# SafeCharge.net
KiCad netlist of a schematic drawn in Altium Designer
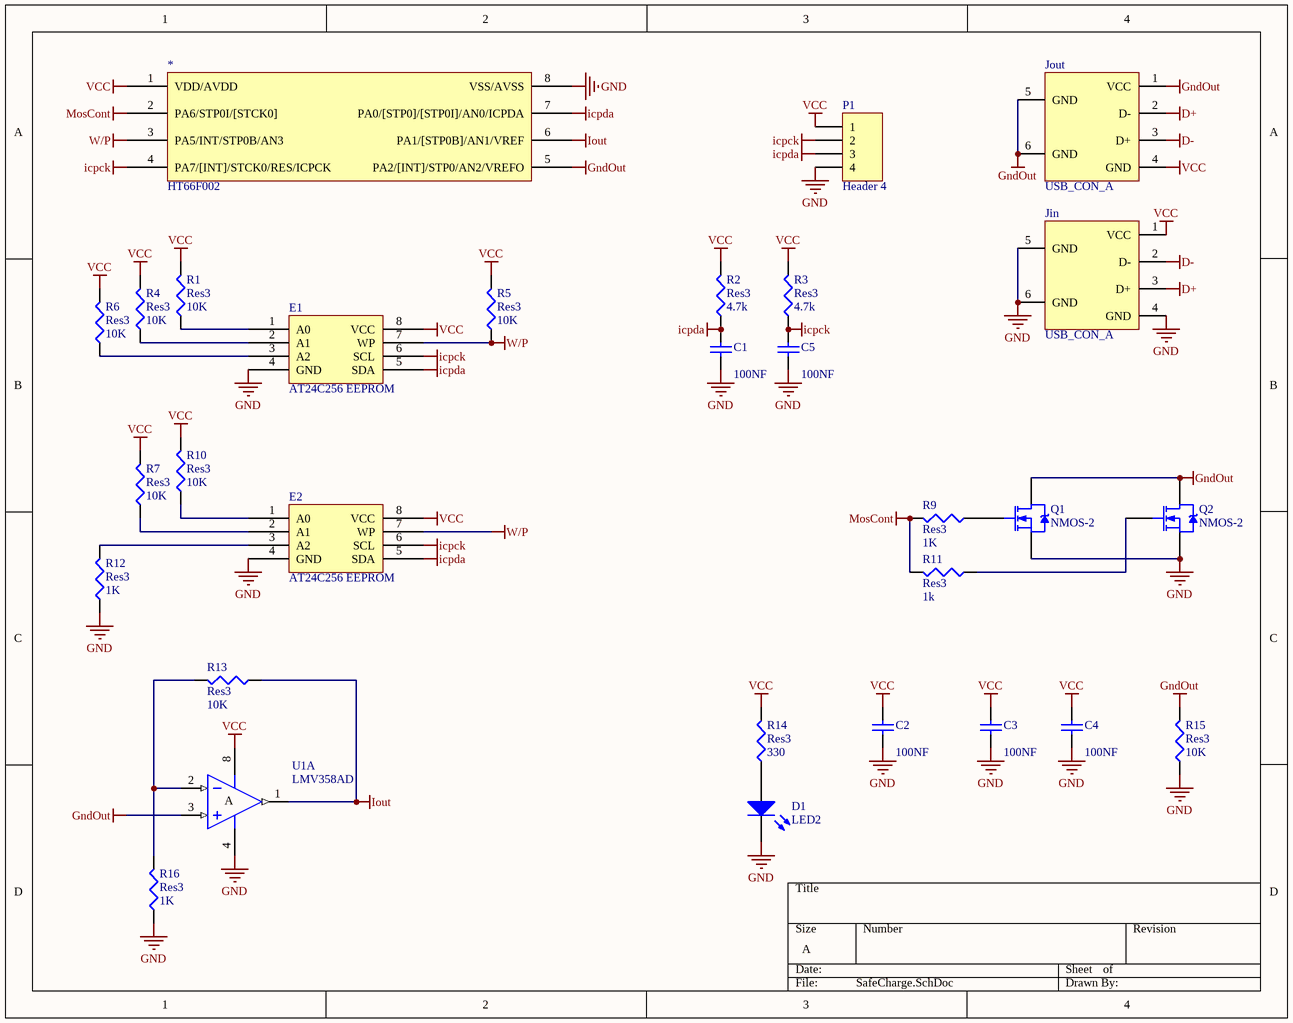
[diagram p0: SafeCharge.SchDoc]

(export (version "E")
  (design (tool "Eeschema 10.0.6"))
  (components
    (comp (ref "*") (value "HT66F002") (footprint "SO8") (libsource (lib "myLib") (part "HT66F002")))
    (comp (ref "C1")
      (value "100NF")
      (footprint "6-0805_N")
      (description "Capacitor (Semiconductor SIM Model)")
      (fields (field (name "Comment") "Cap Semi") (field (name "PUBLISHER") "Altium Limited"))
      (libsource (lib "Miscellaneous Devices") (part "Cap Semi"))
    )
    (comp (ref "C2")
      (value "100NF")
      (footprint "6-0805_N")
      (description "Capacitor (Semiconductor SIM Model)")
      (fields (field (name "Comment") "Cap Semi") (field (name "PUBLISHER") "Altium Limited"))
      (libsource (lib "Miscellaneous Devices") (part "Cap Semi"))
    )
    (comp (ref "C3")
      (value "100NF")
      (footprint "6-0805_N")
      (description "Capacitor (Semiconductor SIM Model)")
      (fields (field (name "Comment") "Cap Semi") (field (name "PUBLISHER") "Altium Limited"))
      (libsource (lib "Miscellaneous Devices") (part "Cap Semi"))
    )
    (comp (ref "C4")
      (value "100NF")
      (footprint "6-0805_N")
      (description "Capacitor (Semiconductor SIM Model)")
      (fields (field (name "Comment") "Cap Semi") (field (name "PUBLISHER") "Altium Limited"))
      (libsource (lib "Miscellaneous Devices") (part "Cap Semi"))
    )
    (comp (ref "C5")
      (value "100NF")
      (footprint "6-0805_N")
      (description "Capacitor (Semiconductor SIM Model)")
      (fields (field (name "Comment") "Cap Semi") (field (name "PUBLISHER") "Altium Limited"))
      (libsource (lib "Miscellaneous Devices") (part "Cap Semi"))
    )
    (comp (ref "D1")
      (value "LED2")
      (footprint "C1206")
      (description "Typical RED, GREEN, YELLOW, AMBER GaAs LED")
      (fields (field (name "PUBLISHER") "Altium Limited"))
      (libsource (lib "Miscellaneous Devices") (part "LED2"))
    )
    (comp (ref "E1")
      (value "AT24C256 EEPROM")
      (footprint "SOIC8_L")
      (libsource (lib "24C256 SHC") (part "AT24C256 EEPROM"))
    )
    (comp (ref "E2")
      (value "AT24C256 EEPROM")
      (footprint "SOIC8_L")
      (libsource (lib "24C256 SHC") (part "AT24C256 EEPROM"))
    )
    (comp (ref "Jin")
      (value "USB_CON_A")
      (footprint "USB_CON_A")
      (libsource (lib "SchLib299") (part "USB_CON_A"))
    )
    (comp (ref "Jout")
      (value "USB_CON_A")
      (footprint "USB_CON_A")
      (libsource (lib "SchLib299") (part "USB_CON_A"))
    )
    (comp (ref "P1")
      (value "Header 4")
      (footprint "HDR1X4")
      (description "Header, 4-Pin")
      (fields (field (name "PUBLISHER") "Altium Limited"))
      (libsource (lib "Miscellaneous Connectors") (part "Header 4"))
    )
    (comp (ref "Q1")
      (value "NMOS-2")
      (footprint "SOT-23_N")
      (description "N-Channel Power MOSFET")
      (fields (field (name "PUBLISHER") "Altium Limited"))
      (libsource (lib "Miscellaneous Devices") (part "NMOS-2"))
    )
    (comp (ref "Q2")
      (value "NMOS-2")
      (footprint "SOT-23_N")
      (description "N-Channel Power MOSFET")
      (fields (field (name "PUBLISHER") "Altium Limited"))
      (libsource (lib "Miscellaneous Devices") (part "NMOS-2"))
    )
    (comp (ref "R1")
      (value "Res3")
      (footprint "6-0805_N")
      (description "Resistor")
      (fields (field (name "ALTIUM_VALUE") "10K") (field (name "PUBLISHER") "Altium Limited"))
      (libsource (lib "Miscellaneous Devices") (part "Res3"))
    )
    (comp (ref "R2")
      (value "Res3")
      (footprint "6-0805_N")
      (description "Resistor")
      (fields (field (name "ALTIUM_VALUE") "4.7k") (field (name "PUBLISHER") "Altium Limited"))
      (libsource (lib "Miscellaneous Devices") (part "Res3"))
    )
    (comp (ref "R3")
      (value "Res3")
      (footprint "6-0805_N")
      (description "Resistor")
      (fields (field (name "ALTIUM_VALUE") "4.7k") (field (name "PUBLISHER") "Altium Limited"))
      (libsource (lib "Miscellaneous Devices") (part "Res3"))
    )
    (comp (ref "R4")
      (value "Res3")
      (footprint "6-0805_N")
      (description "Resistor")
      (fields (field (name "ALTIUM_VALUE") "10K") (field (name "PUBLISHER") "Altium Limited"))
      (libsource (lib "Miscellaneous Devices") (part "Res3"))
    )
    (comp (ref "R5")
      (value "Res3")
      (footprint "6-0805_N")
      (description "Resistor")
      (fields (field (name "ALTIUM_VALUE") "10K") (field (name "PUBLISHER") "Altium Limited"))
      (libsource (lib "Miscellaneous Devices") (part "Res3"))
    )
    (comp (ref "R6")
      (value "Res3")
      (footprint "6-0805_N")
      (description "Resistor")
      (fields (field (name "ALTIUM_VALUE") "10K") (field (name "PUBLISHER") "Altium Limited"))
      (libsource (lib "Miscellaneous Devices") (part "Res3"))
    )
    (comp (ref "R7")
      (value "Res3")
      (footprint "6-0805_N")
      (description "Resistor")
      (fields (field (name "ALTIUM_VALUE") "10K") (field (name "PUBLISHER") "Altium Limited"))
      (libsource (lib "Miscellaneous Devices") (part "Res3"))
    )
    (comp (ref "R9")
      (value "Res3")
      (footprint "6-0805_N")
      (description "Resistor")
      (fields (field (name "ALTIUM_VALUE") "1K") (field (name "PUBLISHER") "Altium Limited"))
      (libsource (lib "Miscellaneous Devices") (part "Res3"))
    )
    (comp (ref "R10")
      (value "Res3")
      (footprint "6-0805_N")
      (description "Resistor")
      (fields (field (name "ALTIUM_VALUE") "10K") (field (name "PUBLISHER") "Altium Limited"))
      (libsource (lib "Miscellaneous Devices") (part "Res3"))
    )
    (comp (ref "R11")
      (value "Res3")
      (footprint "6-0805_N")
      (description "Resistor")
      (fields (field (name "ALTIUM_VALUE") "1k") (field (name "PUBLISHER") "Altium Limited"))
      (libsource (lib "Miscellaneous Devices") (part "Res3"))
    )
    (comp (ref "R12")
      (value "Res3")
      (footprint "6-0805_N")
      (description "Resistor")
      (fields (field (name "ALTIUM_VALUE") "1K") (field (name "PUBLISHER") "Altium Limited"))
      (libsource (lib "Miscellaneous Devices") (part "Res3"))
    )
    (comp (ref "R13")
      (value "Res3")
      (footprint "6-0805_N")
      (description "Resistor")
      (fields (field (name "ALTIUM_VALUE") "10K") (field (name "PUBLISHER") "Altium Limited"))
      (libsource (lib "Miscellaneous Devices") (part "Res3"))
    )
    (comp (ref "R14")
      (value "Res3")
      (footprint "6-0805_N")
      (description "Resistor")
      (fields (field (name "ALTIUM_VALUE") "330") (field (name "PUBLISHER") "Altium Limited"))
      (libsource (lib "Miscellaneous Devices") (part "Res3"))
    )
    (comp (ref "R15")
      (value "Res3")
      (footprint "6-0805_N")
      (description "Resistor")
      (fields (field (name "ALTIUM_VALUE") "10K") (field (name "PUBLISHER") "Altium Limited"))
      (libsource (lib "Miscellaneous Devices") (part "Res3"))
    )
    (comp (ref "R16")
      (value "Res3")
      (footprint "6-0805_N")
      (description "Resistor")
      (fields (field (name "ALTIUM_VALUE") "1K") (field (name "PUBLISHER") "Altium Limited"))
      (libsource (lib "Miscellaneous Devices") (part "Res3"))
    )
    (comp (ref "U1")
      (value "LMV358AD")
      (footprint "SO8_N")
      (description "Low-Power Dual Operational Amplifier")
      (fields (field (name "PUBLISHER") "Altium Limited"))
      (libsource (lib "ST Operational Amplifier") (part "LM358AD"))
    )
  )
  (nets
    (net (code "1") (name "D+") (class "Default")
      (node (ref "Jin") (pin "3") (pinfunction "D+_3") (pintype "passive"))
      (node (ref "Jout") (pin "2") (pinfunction "D-_2") (pintype "passive"))
    )
    (net (code "2") (name "D-") (class "Default")
      (node (ref "Jin") (pin "2") (pinfunction "D-_2") (pintype "passive"))
      (node (ref "Jout") (pin "3") (pinfunction "D+_3") (pintype "passive"))
    )
    (net (code "3") (name "GND") (class "Default")
      (node (ref "*") (pin "8") (pinfunction "VSS/AVSS_8") (pintype "passive"))
      (node (ref "C1") (pin "1") (pinfunction "1_1") (pintype "passive"))
      (node (ref "C2") (pin "1") (pinfunction "1_1") (pintype "passive"))
      (node (ref "C3") (pin "1") (pinfunction "1_1") (pintype "passive"))
      (node (ref "C4") (pin "1") (pinfunction "1_1") (pintype "passive"))
      (node (ref "C5") (pin "1") (pinfunction "1_1") (pintype "passive"))
      (node (ref "D1") (pin "2") (pinfunction "K_2") (pintype "passive"))
      (node (ref "E1") (pin "4") (pinfunction "GND_4") (pintype "passive"))
      (node (ref "E2") (pin "4") (pinfunction "GND_4") (pintype "passive"))
      (node (ref "Jin") (pin "4") (pinfunction "GND_4") (pintype "passive"))
      (node (ref "Jin") (pin "5") (pinfunction "GND_5") (pintype "passive"))
      (node (ref "Jin") (pin "6") (pinfunction "GND_6") (pintype "passive"))
      (node (ref "P1") (pin "4") (pinfunction "4_4") (pintype "passive"))
      (node (ref "Q1") (pin "3") (pinfunction "S_3") (pintype "passive"))
      (node (ref "Q2") (pin "3") (pinfunction "S_3") (pintype "passive"))
      (node (ref "R12") (pin "1") (pinfunction "1_1") (pintype "passive"))
      (node (ref "R15") (pin "1") (pinfunction "1_1") (pintype "passive"))
      (node (ref "R16") (pin "1") (pinfunction "1_1") (pintype "passive"))
      (node (ref "U1") (pin "4") (pinfunction "V-_4") (pintype "power_in"))
    )
    (net (code "4") (name "GndOut") (class "Default")
      (node (ref "*") (pin "5") (pinfunction "PA2/[INT]/STP0/AN2/VREFO_5") (pintype "passive"))
      (node (ref "Jout") (pin "1") (pinfunction "VCC_1") (pintype "passive"))
      (node (ref "Jout") (pin "5") (pinfunction "GND_5") (pintype "passive"))
      (node (ref "Jout") (pin "6") (pinfunction "GND_6") (pintype "passive"))
      (node (ref "Q1") (pin "2") (pinfunction "D_2") (pintype "passive"))
      (node (ref "Q2") (pin "2") (pinfunction "D_2") (pintype "passive"))
      (node (ref "R15") (pin "2") (pinfunction "2_2") (pintype "passive"))
      (node (ref "U1") (pin "3") (pinfunction "IN+_3") (pintype "input"))
    )
    (net (code "5") (name "Iout") (class "Default")
      (node (ref "*") (pin "6") (pinfunction "PA1/[STP0B]/AN1/VREF_6") (pintype "passive"))
      (node (ref "R13") (pin "1") (pinfunction "1_1") (pintype "passive"))
      (node (ref "U1") (pin "1") (pinfunction "OUT_1") (pintype "output"))
    )
    (net (code "6") (name "MosCont") (class "Default")
      (node (ref "*") (pin "2") (pinfunction "PA6/STP0I/[STCK0]_2") (pintype "passive"))
      (node (ref "R11") (pin "2") (pinfunction "2_2") (pintype "passive"))
      (node (ref "R9") (pin "2") (pinfunction "2_2") (pintype "passive"))
    )
    (net (code "7") (name "Net-(D1-A)") (class "Default")
      (node (ref "D1") (pin "1") (pinfunction "A_1") (pintype "passive"))
      (node (ref "R14") (pin "1") (pinfunction "1_1") (pintype "passive"))
    )
    (net (code "8") (name "Net-(E1-A0)") (class "Default")
      (node (ref "E1") (pin "1") (pinfunction "A0_1") (pintype "passive"))
      (node (ref "R1") (pin "1") (pinfunction "1_1") (pintype "passive"))
    )
    (net (code "9") (name "Net-(E1-A1)") (class "Default")
      (node (ref "E1") (pin "2") (pinfunction "A1_2") (pintype "passive"))
      (node (ref "R4") (pin "1") (pinfunction "1_1") (pintype "passive"))
    )
    (net (code "10") (name "Net-(E1-A2)") (class "Default")
      (node (ref "E1") (pin "3") (pinfunction "A2_3") (pintype "passive"))
      (node (ref "R6") (pin "1") (pinfunction "1_1") (pintype "passive"))
    )
    (net (code "11") (name "Net-(E2-A0)") (class "Default")
      (node (ref "E2") (pin "1") (pinfunction "A0_1") (pintype "passive"))
      (node (ref "R10") (pin "1") (pinfunction "1_1") (pintype "passive"))
    )
    (net (code "12") (name "Net-(E2-A1)") (class "Default")
      (node (ref "E2") (pin "2") (pinfunction "A1_2") (pintype "passive"))
      (node (ref "R7") (pin "1") (pinfunction "1_1") (pintype "passive"))
    )
    (net (code "13") (name "Net-(E2-A2)") (class "Default")
      (node (ref "E2") (pin "3") (pinfunction "A2_3") (pintype "passive"))
      (node (ref "R12") (pin "2") (pinfunction "2_2") (pintype "passive"))
    )
    (net (code "14") (name "Net-(Q1-G)") (class "Default")
      (node (ref "Q1") (pin "1") (pinfunction "G_1") (pintype "passive"))
      (node (ref "R9") (pin "1") (pinfunction "1_1") (pintype "passive"))
    )
    (net (code "15") (name "Net-(Q2-G)") (class "Default")
      (node (ref "Q2") (pin "1") (pinfunction "G_1") (pintype "passive"))
      (node (ref "R11") (pin "1") (pinfunction "1_1") (pintype "passive"))
    )
    (net (code "16") (name "Net-(U1A-IN-)") (class "Default")
      (node (ref "R13") (pin "2") (pinfunction "2_2") (pintype "passive"))
      (node (ref "R16") (pin "2") (pinfunction "2_2") (pintype "passive"))
      (node (ref "U1") (pin "2") (pinfunction "IN-_2") (pintype "input"))
    )
    (net (code "17") (name "VCC") (class "Default")
      (node (ref "*") (pin "1") (pinfunction "VDD/AVDD_1") (pintype "passive"))
      (node (ref "C2") (pin "2") (pinfunction "2_2") (pintype "passive"))
      (node (ref "C3") (pin "2") (pinfunction "2_2") (pintype "passive"))
      (node (ref "C4") (pin "2") (pinfunction "2_2") (pintype "passive"))
      (node (ref "E1") (pin "8") (pinfunction "VCC_8") (pintype "passive"))
      (node (ref "E2") (pin "8") (pinfunction "VCC_8") (pintype "passive"))
      (node (ref "Jin") (pin "1") (pinfunction "VCC_1") (pintype "passive"))
      (node (ref "Jout") (pin "4") (pinfunction "GND_4") (pintype "passive"))
      (node (ref "P1") (pin "1") (pinfunction "1_1") (pintype "passive"))
      (node (ref "R1") (pin "2") (pinfunction "2_2") (pintype "passive"))
      (node (ref "R10") (pin "2") (pinfunction "2_2") (pintype "passive"))
      (node (ref "R14") (pin "2") (pinfunction "2_2") (pintype "passive"))
      (node (ref "R2") (pin "2") (pinfunction "2_2") (pintype "passive"))
      (node (ref "R3") (pin "2") (pinfunction "2_2") (pintype "passive"))
      (node (ref "R4") (pin "2") (pinfunction "2_2") (pintype "passive"))
      (node (ref "R5") (pin "2") (pinfunction "2_2") (pintype "passive"))
      (node (ref "R6") (pin "2") (pinfunction "2_2") (pintype "passive"))
      (node (ref "R7") (pin "2") (pinfunction "2_2") (pintype "passive"))
      (node (ref "U1") (pin "8") (pinfunction "V+_8") (pintype "power_in"))
    )
    (net (code "18") (name "W{slash}P") (class "Default")
      (node (ref "*") (pin "3") (pinfunction "PA5/INT/STP0B/AN3_3") (pintype "passive"))
      (node (ref "E1") (pin "7") (pinfunction "WP_7") (pintype "passive"))
      (node (ref "E2") (pin "7") (pinfunction "WP_7") (pintype "passive"))
      (node (ref "R5") (pin "1") (pinfunction "1_1") (pintype "passive"))
    )
    (net (code "19") (name "icpck") (class "Default")
      (node (ref "*") (pin "4") (pinfunction "PA7/[INT]/STCK0/RES/ICPCK_4") (pintype "passive"))
      (node (ref "C5") (pin "2") (pinfunction "2_2") (pintype "passive"))
      (node (ref "E1") (pin "6") (pinfunction "SCL_6") (pintype "passive"))
      (node (ref "E2") (pin "6") (pinfunction "SCL_6") (pintype "passive"))
      (node (ref "P1") (pin "2") (pinfunction "2_2") (pintype "passive"))
      (node (ref "R3") (pin "1") (pinfunction "1_1") (pintype "passive"))
    )
    (net (code "20") (name "icpda") (class "Default")
      (node (ref "*") (pin "7") (pinfunction "PA0/[STP0]/[STP0I]/AN0/ICPDA_7") (pintype "passive"))
      (node (ref "C1") (pin "2") (pinfunction "2_2") (pintype "passive"))
      (node (ref "E1") (pin "5") (pinfunction "SDA_5") (pintype "passive"))
      (node (ref "E2") (pin "5") (pinfunction "SDA_5") (pintype "passive"))
      (node (ref "P1") (pin "3") (pinfunction "3_3") (pintype "passive"))
      (node (ref "R2") (pin "1") (pinfunction "1_1") (pintype "passive"))
    )
  )
)
